# demux1-10.net
KiCad netlist of a schematic drawn in Altium Designer
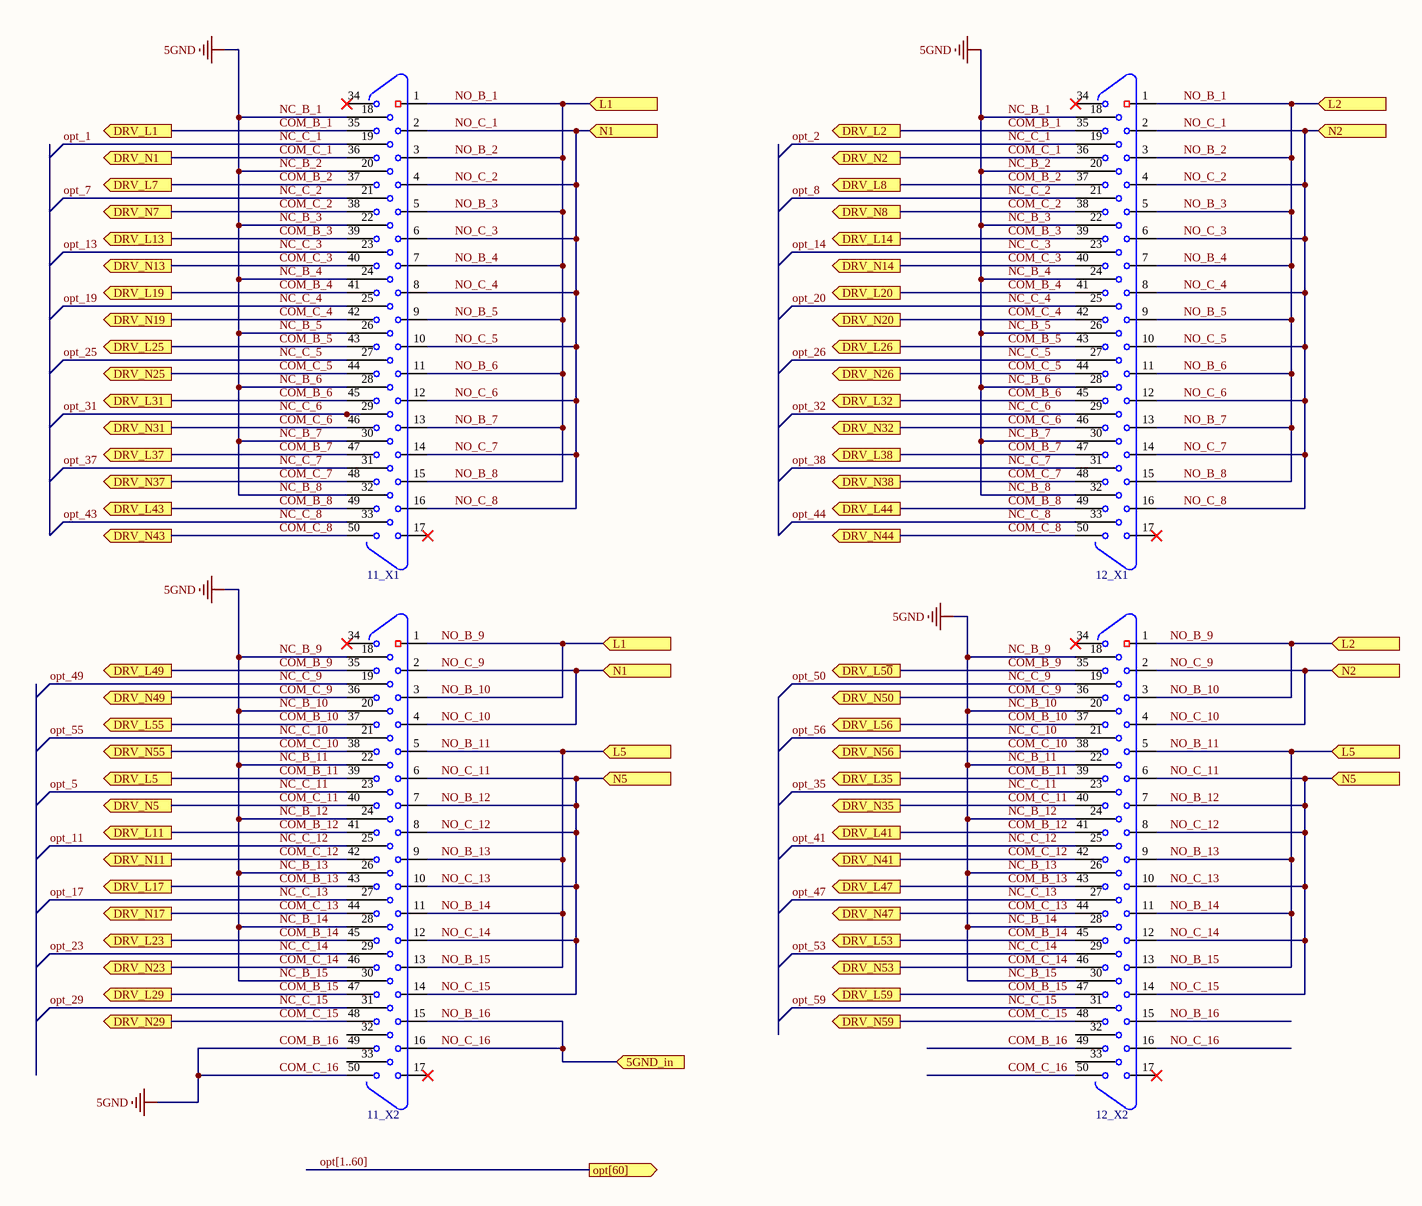
[diagram p0: demux1-10.SchDoc, left]
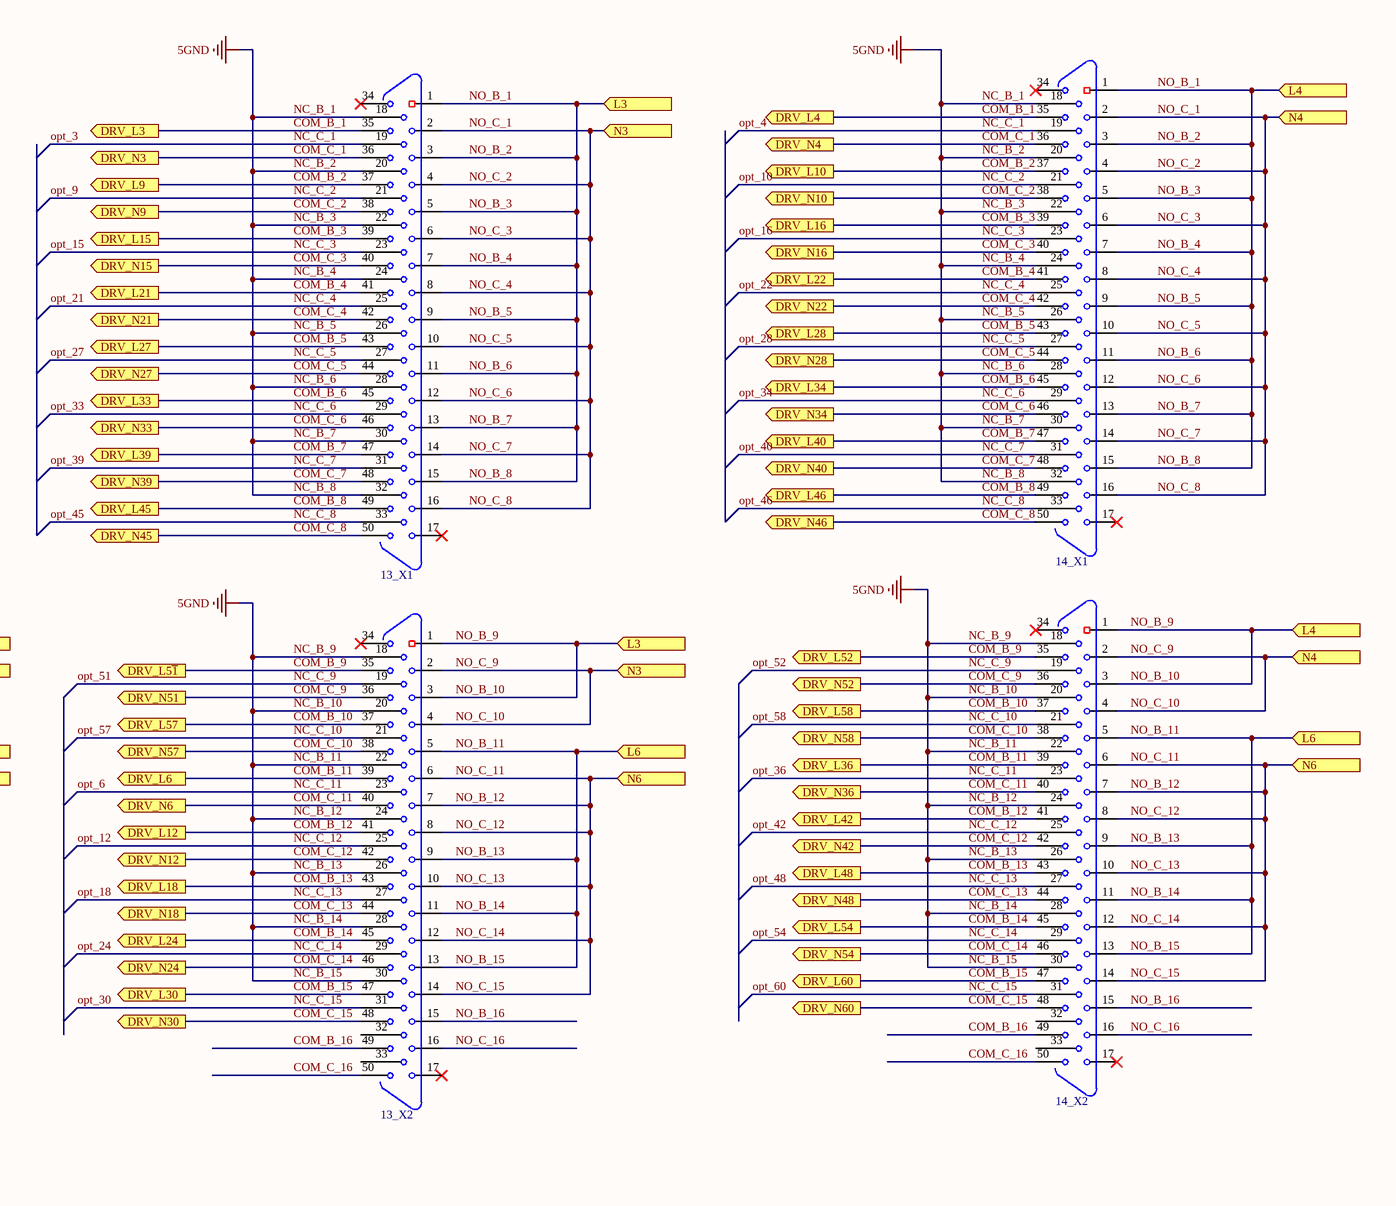
[diagram p1: demux1-10.SchDoc, right]

(export (version "E")
  (design (tool "Eeschema 10.0.6"))
  (components
    (comp (ref "11_X1") (value "DB50") (footprint "DB50_RA") (libsource (lib "WIRE") (part "DB50")))
    (comp (ref "11_X2") (value "DB50") (footprint "DB50_RA") (libsource (lib "WIRE") (part "DB50")))
    (comp (ref "12_X1") (value "DB50") (footprint "DB50_RA") (libsource (lib "WIRE") (part "DB50")))
    (comp (ref "12_X2") (value "DB50") (footprint "DB50_RA") (libsource (lib "WIRE") (part "DB50")))
    (comp (ref "13_X1") (value "DB50") (footprint "DB50_RA") (libsource (lib "WIRE") (part "DB50")))
    (comp (ref "13_X2") (value "DB50") (footprint "DB50_RA") (libsource (lib "WIRE") (part "DB50")))
    (comp (ref "14_X1") (value "DB50") (footprint "DB50_RA") (libsource (lib "WIRE") (part "DB50")))
    (comp (ref "14_X2") (value "DB50") (footprint "DB50_RA") (libsource (lib "WIRE") (part "DB50")))
  )
  (nets
    (net (code "61") (name "/COM_B_1") (class "Default")
      (node (ref "11_X1") (pin "35") (pinfunction "35_35") (pintype "passive"))
      (node (ref "12_X1") (pin "35") (pinfunction "35_35") (pintype "passive"))
      (node (ref "13_X1") (pin "35") (pinfunction "35_35") (pintype "passive"))
      (node (ref "14_X1") (pin "35") (pinfunction "35_35") (pintype "passive"))
    )
    (net (code "62") (name "/COM_B_2") (class "Default")
      (node (ref "11_X1") (pin "37") (pinfunction "37_37") (pintype "passive"))
      (node (ref "12_X1") (pin "37") (pinfunction "37_37") (pintype "passive"))
      (node (ref "13_X1") (pin "37") (pinfunction "37_37") (pintype "passive"))
      (node (ref "14_X1") (pin "37") (pinfunction "37_37") (pintype "passive"))
    )
    (net (code "63") (name "/COM_B_3") (class "Default")
      (node (ref "11_X1") (pin "39") (pinfunction "39_39") (pintype "passive"))
      (node (ref "12_X1") (pin "39") (pinfunction "39_39") (pintype "passive"))
      (node (ref "13_X1") (pin "39") (pinfunction "39_39") (pintype "passive"))
      (node (ref "14_X1") (pin "39") (pinfunction "39_39") (pintype "passive"))
    )
    (net (code "64") (name "/COM_B_4") (class "Default")
      (node (ref "11_X1") (pin "41") (pinfunction "41_41") (pintype "passive"))
      (node (ref "12_X1") (pin "41") (pinfunction "41_41") (pintype "passive"))
      (node (ref "13_X1") (pin "41") (pinfunction "41_41") (pintype "passive"))
      (node (ref "14_X1") (pin "41") (pinfunction "41_41") (pintype "passive"))
    )
    (net (code "65") (name "/COM_B_5") (class "Default")
      (node (ref "11_X1") (pin "43") (pinfunction "43_43") (pintype "passive"))
      (node (ref "12_X1") (pin "43") (pinfunction "43_43") (pintype "passive"))
      (node (ref "13_X1") (pin "43") (pinfunction "43_43") (pintype "passive"))
      (node (ref "14_X1") (pin "43") (pinfunction "43_43") (pintype "passive"))
    )
    (net (code "66") (name "/COM_B_6") (class "Default")
      (node (ref "11_X1") (pin "45") (pinfunction "45_45") (pintype "passive"))
      (node (ref "12_X1") (pin "45") (pinfunction "45_45") (pintype "passive"))
      (node (ref "13_X1") (pin "45") (pinfunction "45_45") (pintype "passive"))
      (node (ref "14_X1") (pin "45") (pinfunction "45_45") (pintype "passive"))
    )
    (net (code "67") (name "/COM_B_7") (class "Default")
      (node (ref "11_X1") (pin "47") (pinfunction "47_47") (pintype "passive"))
      (node (ref "12_X1") (pin "47") (pinfunction "47_47") (pintype "passive"))
      (node (ref "13_X1") (pin "47") (pinfunction "47_47") (pintype "passive"))
      (node (ref "14_X1") (pin "47") (pinfunction "47_47") (pintype "passive"))
    )
    (net (code "68") (name "/COM_B_8") (class "Default")
      (node (ref "11_X1") (pin "49") (pinfunction "49_49") (pintype "passive"))
      (node (ref "12_X1") (pin "49") (pinfunction "49_49") (pintype "passive"))
      (node (ref "13_X1") (pin "49") (pinfunction "49_49") (pintype "passive"))
      (node (ref "14_X1") (pin "49") (pinfunction "49_49") (pintype "passive"))
    )
    (net (code "69") (name "/COM_B_9") (class "Default")
      (node (ref "11_X2") (pin "35") (pinfunction "35_35") (pintype "passive"))
      (node (ref "12_X2") (pin "35") (pinfunction "35_35") (pintype "passive"))
      (node (ref "13_X2") (pin "35") (pinfunction "35_35") (pintype "passive"))
      (node (ref "14_X2") (pin "35") (pinfunction "35_35") (pintype "passive"))
    )
    (net (code "70") (name "/COM_B_10") (class "Default")
      (node (ref "11_X2") (pin "37") (pinfunction "37_37") (pintype "passive"))
      (node (ref "12_X2") (pin "37") (pinfunction "37_37") (pintype "passive"))
      (node (ref "13_X2") (pin "37") (pinfunction "37_37") (pintype "passive"))
      (node (ref "14_X2") (pin "37") (pinfunction "37_37") (pintype "passive"))
    )
    (net (code "71") (name "/COM_B_11") (class "Default")
      (node (ref "11_X2") (pin "39") (pinfunction "39_39") (pintype "passive"))
      (node (ref "12_X2") (pin "39") (pinfunction "39_39") (pintype "passive"))
      (node (ref "13_X2") (pin "39") (pinfunction "39_39") (pintype "passive"))
      (node (ref "14_X2") (pin "39") (pinfunction "39_39") (pintype "passive"))
    )
    (net (code "72") (name "/COM_B_12") (class "Default")
      (node (ref "11_X2") (pin "41") (pinfunction "41_41") (pintype "passive"))
      (node (ref "12_X2") (pin "41") (pinfunction "41_41") (pintype "passive"))
      (node (ref "13_X2") (pin "41") (pinfunction "41_41") (pintype "passive"))
      (node (ref "14_X2") (pin "41") (pinfunction "41_41") (pintype "passive"))
    )
    (net (code "73") (name "/COM_B_13") (class "Default")
      (node (ref "11_X2") (pin "43") (pinfunction "43_43") (pintype "passive"))
      (node (ref "12_X2") (pin "43") (pinfunction "43_43") (pintype "passive"))
      (node (ref "13_X2") (pin "43") (pinfunction "43_43") (pintype "passive"))
      (node (ref "14_X2") (pin "43") (pinfunction "43_43") (pintype "passive"))
    )
    (net (code "74") (name "/COM_B_14") (class "Default")
      (node (ref "11_X2") (pin "45") (pinfunction "45_45") (pintype "passive"))
      (node (ref "12_X2") (pin "45") (pinfunction "45_45") (pintype "passive"))
      (node (ref "13_X2") (pin "45") (pinfunction "45_45") (pintype "passive"))
      (node (ref "14_X2") (pin "45") (pinfunction "45_45") (pintype "passive"))
    )
    (net (code "75") (name "/COM_B_15") (class "Default")
      (node (ref "11_X2") (pin "47") (pinfunction "47_47") (pintype "passive"))
      (node (ref "12_X2") (pin "47") (pinfunction "47_47") (pintype "passive"))
      (node (ref "13_X2") (pin "47") (pinfunction "47_47") (pintype "passive"))
      (node (ref "14_X2") (pin "47") (pinfunction "47_47") (pintype "passive"))
    )
    (net (code "76") (name "/COM_C_1") (class "Default")
      (node (ref "11_X1") (pin "36") (pinfunction "36_36") (pintype "passive"))
      (node (ref "12_X1") (pin "36") (pinfunction "36_36") (pintype "passive"))
      (node (ref "13_X1") (pin "36") (pinfunction "36_36") (pintype "passive"))
      (node (ref "14_X1") (pin "36") (pinfunction "36_36") (pintype "passive"))
    )
    (net (code "77") (name "/COM_C_2") (class "Default")
      (node (ref "11_X1") (pin "38") (pinfunction "38_38") (pintype "passive"))
      (node (ref "12_X1") (pin "38") (pinfunction "38_38") (pintype "passive"))
      (node (ref "13_X1") (pin "38") (pinfunction "38_38") (pintype "passive"))
      (node (ref "14_X1") (pin "38") (pinfunction "38_38") (pintype "passive"))
    )
    (net (code "78") (name "/COM_C_3") (class "Default")
      (node (ref "11_X1") (pin "40") (pinfunction "40_40") (pintype "passive"))
      (node (ref "12_X1") (pin "40") (pinfunction "40_40") (pintype "passive"))
      (node (ref "13_X1") (pin "40") (pinfunction "40_40") (pintype "passive"))
      (node (ref "14_X1") (pin "40") (pinfunction "40_40") (pintype "passive"))
    )
    (net (code "79") (name "/COM_C_4") (class "Default")
      (node (ref "11_X1") (pin "42") (pinfunction "42_42") (pintype "passive"))
      (node (ref "12_X1") (pin "42") (pinfunction "42_42") (pintype "passive"))
      (node (ref "13_X1") (pin "42") (pinfunction "42_42") (pintype "passive"))
      (node (ref "14_X1") (pin "42") (pinfunction "42_42") (pintype "passive"))
    )
    (net (code "80") (name "/COM_C_5") (class "Default")
      (node (ref "11_X1") (pin "44") (pinfunction "44_44") (pintype "passive"))
      (node (ref "12_X1") (pin "44") (pinfunction "44_44") (pintype "passive"))
      (node (ref "13_X1") (pin "44") (pinfunction "44_44") (pintype "passive"))
      (node (ref "14_X1") (pin "44") (pinfunction "44_44") (pintype "passive"))
    )
    (net (code "81") (name "/COM_C_6") (class "Default")
      (node (ref "11_X1") (pin "46") (pinfunction "46_46") (pintype "passive"))
      (node (ref "12_X1") (pin "46") (pinfunction "46_46") (pintype "passive"))
      (node (ref "13_X1") (pin "46") (pinfunction "46_46") (pintype "passive"))
      (node (ref "14_X1") (pin "46") (pinfunction "46_46") (pintype "passive"))
    )
    (net (code "82") (name "/COM_C_7") (class "Default")
      (node (ref "11_X1") (pin "48") (pinfunction "48_48") (pintype "passive"))
      (node (ref "12_X1") (pin "48") (pinfunction "48_48") (pintype "passive"))
      (node (ref "13_X1") (pin "48") (pinfunction "48_48") (pintype "passive"))
      (node (ref "14_X1") (pin "48") (pinfunction "48_48") (pintype "passive"))
    )
    (net (code "83") (name "/COM_C_8") (class "Default")
      (node (ref "11_X1") (pin "50") (pinfunction "50_50") (pintype "passive"))
      (node (ref "12_X1") (pin "50") (pinfunction "50_50") (pintype "passive"))
      (node (ref "13_X1") (pin "50") (pinfunction "50_50") (pintype "passive"))
      (node (ref "14_X1") (pin "50") (pinfunction "50_50") (pintype "passive"))
    )
    (net (code "84") (name "/COM_C_9") (class "Default")
      (node (ref "11_X2") (pin "36") (pinfunction "36_36") (pintype "passive"))
      (node (ref "12_X2") (pin "36") (pinfunction "36_36") (pintype "passive"))
      (node (ref "13_X2") (pin "36") (pinfunction "36_36") (pintype "passive"))
      (node (ref "14_X2") (pin "36") (pinfunction "36_36") (pintype "passive"))
    )
    (net (code "85") (name "/COM_C_10") (class "Default")
      (node (ref "11_X2") (pin "38") (pinfunction "38_38") (pintype "passive"))
      (node (ref "12_X2") (pin "38") (pinfunction "38_38") (pintype "passive"))
      (node (ref "13_X2") (pin "38") (pinfunction "38_38") (pintype "passive"))
      (node (ref "14_X2") (pin "38") (pinfunction "38_38") (pintype "passive"))
    )
    (net (code "86") (name "/COM_C_11") (class "Default")
      (node (ref "11_X2") (pin "40") (pinfunction "40_40") (pintype "passive"))
      (node (ref "12_X2") (pin "40") (pinfunction "40_40") (pintype "passive"))
      (node (ref "13_X2") (pin "40") (pinfunction "40_40") (pintype "passive"))
      (node (ref "14_X2") (pin "40") (pinfunction "40_40") (pintype "passive"))
    )
    (net (code "87") (name "/COM_C_12") (class "Default")
      (node (ref "11_X2") (pin "42") (pinfunction "42_42") (pintype "passive"))
      (node (ref "12_X2") (pin "42") (pinfunction "42_42") (pintype "passive"))
      (node (ref "13_X2") (pin "42") (pinfunction "42_42") (pintype "passive"))
      (node (ref "14_X2") (pin "42") (pinfunction "42_42") (pintype "passive"))
    )
    (net (code "88") (name "/COM_C_13") (class "Default")
      (node (ref "11_X2") (pin "44") (pinfunction "44_44") (pintype "passive"))
      (node (ref "12_X2") (pin "44") (pinfunction "44_44") (pintype "passive"))
      (node (ref "13_X2") (pin "44") (pinfunction "44_44") (pintype "passive"))
      (node (ref "14_X2") (pin "44") (pinfunction "44_44") (pintype "passive"))
    )
    (net (code "89") (name "/COM_C_14") (class "Default")
      (node (ref "11_X2") (pin "46") (pinfunction "46_46") (pintype "passive"))
      (node (ref "12_X2") (pin "46") (pinfunction "46_46") (pintype "passive"))
      (node (ref "13_X2") (pin "46") (pinfunction "46_46") (pintype "passive"))
      (node (ref "14_X2") (pin "46") (pinfunction "46_46") (pintype "passive"))
    )
    (net (code "90") (name "/COM_C_15") (class "Default")
      (node (ref "11_X2") (pin "48") (pinfunction "48_48") (pintype "passive"))
      (node (ref "12_X2") (pin "48") (pinfunction "48_48") (pintype "passive"))
      (node (ref "13_X2") (pin "48") (pinfunction "48_48") (pintype "passive"))
      (node (ref "14_X2") (pin "48") (pinfunction "48_48") (pintype "passive"))
    )
    (net (code "91") (name "/NC_C_1") (class "Default")
      (node (ref "11_X1") (pin "19") (pinfunction "19_19") (pintype "passive"))
      (node (ref "12_X1") (pin "19") (pinfunction "19_19") (pintype "passive"))
      (node (ref "13_X1") (pin "19") (pinfunction "19_19") (pintype "passive"))
      (node (ref "14_X1") (pin "19") (pinfunction "19_19") (pintype "passive"))
    )
    (net (code "92") (name "/NC_C_2") (class "Default")
      (node (ref "11_X1") (pin "21") (pinfunction "21_21") (pintype "passive"))
      (node (ref "12_X1") (pin "21") (pinfunction "21_21") (pintype "passive"))
      (node (ref "13_X1") (pin "21") (pinfunction "21_21") (pintype "passive"))
      (node (ref "14_X1") (pin "21") (pinfunction "21_21") (pintype "passive"))
    )
    (net (code "93") (name "/NC_C_3") (class "Default")
      (node (ref "11_X1") (pin "23") (pinfunction "23_23") (pintype "passive"))
      (node (ref "12_X1") (pin "23") (pinfunction "23_23") (pintype "passive"))
      (node (ref "13_X1") (pin "23") (pinfunction "23_23") (pintype "passive"))
      (node (ref "14_X1") (pin "23") (pinfunction "23_23") (pintype "passive"))
    )
    (net (code "94") (name "/NC_C_4") (class "Default")
      (node (ref "11_X1") (pin "25") (pinfunction "3_25") (pintype "passive"))
      (node (ref "12_X1") (pin "25") (pinfunction "3_25") (pintype "passive"))
      (node (ref "13_X1") (pin "25") (pinfunction "3_25") (pintype "passive"))
      (node (ref "14_X1") (pin "25") (pinfunction "3_25") (pintype "passive"))
    )
    (net (code "95") (name "/NC_C_5") (class "Default")
      (node (ref "11_X1") (pin "27") (pinfunction "27_27") (pintype "passive"))
      (node (ref "12_X1") (pin "27") (pinfunction "27_27") (pintype "passive"))
      (node (ref "13_X1") (pin "27") (pinfunction "27_27") (pintype "passive"))
      (node (ref "14_X1") (pin "27") (pinfunction "27_27") (pintype "passive"))
    )
    (net (code "96") (name "/NC_C_6") (class "Default")
      (node (ref "11_X1") (pin "29") (pinfunction "29_29") (pintype "passive"))
      (node (ref "12_X1") (pin "29") (pinfunction "29_29") (pintype "passive"))
      (node (ref "13_X1") (pin "29") (pinfunction "29_29") (pintype "passive"))
      (node (ref "14_X1") (pin "29") (pinfunction "29_29") (pintype "passive"))
    )
    (net (code "97") (name "/NC_C_7") (class "Default")
      (node (ref "11_X1") (pin "31") (pinfunction "31_31") (pintype "passive"))
      (node (ref "12_X1") (pin "31") (pinfunction "31_31") (pintype "passive"))
      (node (ref "13_X1") (pin "31") (pinfunction "31_31") (pintype "passive"))
      (node (ref "14_X1") (pin "31") (pinfunction "31_31") (pintype "passive"))
    )
    (net (code "98") (name "/NC_C_8") (class "Default")
      (node (ref "11_X1") (pin "33") (pinfunction "33_33") (pintype "passive"))
      (node (ref "12_X1") (pin "33") (pinfunction "33_33") (pintype "passive"))
      (node (ref "13_X1") (pin "33") (pinfunction "33_33") (pintype "passive"))
      (node (ref "14_X1") (pin "33") (pinfunction "33_33") (pintype "passive"))
    )
    (net (code "99") (name "/NC_C_9") (class "Default")
      (node (ref "11_X2") (pin "19") (pinfunction "19_19") (pintype "passive"))
      (node (ref "12_X2") (pin "19") (pinfunction "19_19") (pintype "passive"))
      (node (ref "13_X2") (pin "19") (pinfunction "19_19") (pintype "passive"))
      (node (ref "14_X2") (pin "19") (pinfunction "19_19") (pintype "passive"))
    )
    (net (code "100") (name "/NC_C_10") (class "Default")
      (node (ref "11_X2") (pin "21") (pinfunction "21_21") (pintype "passive"))
      (node (ref "12_X2") (pin "21") (pinfunction "21_21") (pintype "passive"))
      (node (ref "13_X2") (pin "21") (pinfunction "21_21") (pintype "passive"))
      (node (ref "14_X2") (pin "21") (pinfunction "21_21") (pintype "passive"))
    )
    (net (code "101") (name "/NC_C_11") (class "Default")
      (node (ref "11_X2") (pin "23") (pinfunction "23_23") (pintype "passive"))
      (node (ref "12_X2") (pin "23") (pinfunction "23_23") (pintype "passive"))
      (node (ref "13_X2") (pin "23") (pinfunction "23_23") (pintype "passive"))
      (node (ref "14_X2") (pin "23") (pinfunction "23_23") (pintype "passive"))
    )
    (net (code "102") (name "/NC_C_12") (class "Default")
      (node (ref "11_X2") (pin "25") (pinfunction "3_25") (pintype "passive"))
      (node (ref "12_X2") (pin "25") (pinfunction "3_25") (pintype "passive"))
      (node (ref "13_X2") (pin "25") (pinfunction "3_25") (pintype "passive"))
      (node (ref "14_X2") (pin "25") (pinfunction "3_25") (pintype "passive"))
    )
    (net (code "103") (name "/NC_C_13") (class "Default")
      (node (ref "11_X2") (pin "27") (pinfunction "27_27") (pintype "passive"))
      (node (ref "12_X2") (pin "27") (pinfunction "27_27") (pintype "passive"))
      (node (ref "13_X2") (pin "27") (pinfunction "27_27") (pintype "passive"))
      (node (ref "14_X2") (pin "27") (pinfunction "27_27") (pintype "passive"))
    )
    (net (code "104") (name "/NC_C_14") (class "Default")
      (node (ref "11_X2") (pin "29") (pinfunction "29_29") (pintype "passive"))
      (node (ref "12_X2") (pin "29") (pinfunction "29_29") (pintype "passive"))
      (node (ref "13_X2") (pin "29") (pinfunction "29_29") (pintype "passive"))
      (node (ref "14_X2") (pin "29") (pinfunction "29_29") (pintype "passive"))
    )
    (net (code "105") (name "/NC_C_15") (class "Default")
      (node (ref "11_X2") (pin "31") (pinfunction "31_31") (pintype "passive"))
      (node (ref "12_X2") (pin "31") (pinfunction "31_31") (pintype "passive"))
      (node (ref "13_X2") (pin "31") (pinfunction "31_31") (pintype "passive"))
      (node (ref "14_X2") (pin "31") (pinfunction "31_31") (pintype "passive"))
    )
    (net (code "106") (name "/NO_B_1") (class "Default")
      (node (ref "11_X1") (pin "1") (pinfunction "1_1") (pintype "passive"))
      (node (ref "11_X1") (pin "11") (pinfunction "11_11") (pintype "passive"))
      (node (ref "11_X1") (pin "13") (pinfunction "13_13") (pintype "passive"))
      (node (ref "11_X1") (pin "15") (pinfunction "15_15") (pintype "passive"))
      (node (ref "11_X1") (pin "3") (pinfunction "3_3") (pintype "passive"))
      (node (ref "11_X1") (pin "5") (pinfunction "2_5") (pintype "passive"))
      (node (ref "11_X1") (pin "7") (pinfunction "7_7") (pintype "passive"))
      (node (ref "11_X1") (pin "9") (pinfunction "4_9") (pintype "passive"))
      (node (ref "11_X2") (pin "1") (pinfunction "1_1") (pintype "passive"))
      (node (ref "11_X2") (pin "3") (pinfunction "3_3") (pintype "passive"))
      (node (ref "12_X1") (pin "1") (pinfunction "1_1") (pintype "passive"))
      (node (ref "12_X1") (pin "11") (pinfunction "11_11") (pintype "passive"))
      (node (ref "12_X1") (pin "13") (pinfunction "13_13") (pintype "passive"))
      (node (ref "12_X1") (pin "15") (pinfunction "15_15") (pintype "passive"))
      (node (ref "12_X1") (pin "3") (pinfunction "3_3") (pintype "passive"))
      (node (ref "12_X1") (pin "5") (pinfunction "2_5") (pintype "passive"))
      (node (ref "12_X1") (pin "7") (pinfunction "7_7") (pintype "passive"))
      (node (ref "12_X1") (pin "9") (pinfunction "4_9") (pintype "passive"))
      (node (ref "12_X2") (pin "1") (pinfunction "1_1") (pintype "passive"))
      (node (ref "12_X2") (pin "3") (pinfunction "3_3") (pintype "passive"))
      (node (ref "13_X1") (pin "1") (pinfunction "1_1") (pintype "passive"))
      (node (ref "13_X1") (pin "11") (pinfunction "11_11") (pintype "passive"))
      (node (ref "13_X1") (pin "13") (pinfunction "13_13") (pintype "passive"))
      (node (ref "13_X1") (pin "15") (pinfunction "15_15") (pintype "passive"))
      (node (ref "13_X1") (pin "3") (pinfunction "3_3") (pintype "passive"))
      (node (ref "13_X1") (pin "5") (pinfunction "2_5") (pintype "passive"))
      (node (ref "13_X1") (pin "7") (pinfunction "7_7") (pintype "passive"))
      (node (ref "13_X1") (pin "9") (pinfunction "4_9") (pintype "passive"))
      (node (ref "13_X2") (pin "1") (pinfunction "1_1") (pintype "passive"))
      (node (ref "13_X2") (pin "3") (pinfunction "3_3") (pintype "passive"))
      (node (ref "14_X1") (pin "1") (pinfunction "1_1") (pintype "passive"))
      (node (ref "14_X1") (pin "11") (pinfunction "11_11") (pintype "passive"))
      (node (ref "14_X1") (pin "13") (pinfunction "13_13") (pintype "passive"))
      (node (ref "14_X1") (pin "15") (pinfunction "15_15") (pintype "passive"))
      (node (ref "14_X1") (pin "3") (pinfunction "3_3") (pintype "passive"))
      (node (ref "14_X1") (pin "5") (pinfunction "2_5") (pintype "passive"))
      (node (ref "14_X1") (pin "7") (pinfunction "7_7") (pintype "passive"))
      (node (ref "14_X1") (pin "9") (pinfunction "4_9") (pintype "passive"))
      (node (ref "14_X2") (pin "1") (pinfunction "1_1") (pintype "passive"))
      (node (ref "14_X2") (pin "3") (pinfunction "3_3") (pintype "passive"))
    )
    (net (code "107") (name "/NO_B_11") (class "Default")
      (node (ref "11_X2") (pin "11") (pinfunction "11_11") (pintype "passive"))
      (node (ref "11_X2") (pin "13") (pinfunction "13_13") (pintype "passive"))
      (node (ref "11_X2") (pin "5") (pinfunction "2_5") (pintype "passive"))
      (node (ref "11_X2") (pin "9") (pinfunction "4_9") (pintype "passive"))
      (node (ref "12_X2") (pin "11") (pinfunction "11_11") (pintype "passive"))
      (node (ref "12_X2") (pin "13") (pinfunction "13_13") (pintype "passive"))
      (node (ref "12_X2") (pin "5") (pinfunction "2_5") (pintype "passive"))
      (node (ref "12_X2") (pin "9") (pinfunction "4_9") (pintype "passive"))
      (node (ref "13_X2") (pin "11") (pinfunction "11_11") (pintype "passive"))
      (node (ref "13_X2") (pin "13") (pinfunction "13_13") (pintype "passive"))
      (node (ref "13_X2") (pin "5") (pinfunction "2_5") (pintype "passive"))
      (node (ref "13_X2") (pin "9") (pinfunction "4_9") (pintype "passive"))
      (node (ref "14_X2") (pin "11") (pinfunction "11_11") (pintype "passive"))
      (node (ref "14_X2") (pin "13") (pinfunction "13_13") (pintype "passive"))
      (node (ref "14_X2") (pin "5") (pinfunction "2_5") (pintype "passive"))
      (node (ref "14_X2") (pin "9") (pinfunction "4_9") (pintype "passive"))
    )
    (net (code "108") (name "/NO_B_12") (class "Default")
      (node (ref "11_X2") (pin "10") (pinfunction "10_10") (pintype "passive"))
      (node (ref "11_X2") (pin "12") (pinfunction "12_12") (pintype "passive"))
      (node (ref "11_X2") (pin "14") (pinfunction "14_14") (pintype "passive"))
      (node (ref "11_X2") (pin "6") (pinfunction "6_6") (pintype "passive"))
      (node (ref "11_X2") (pin "7") (pinfunction "7_7") (pintype "passive"))
      (node (ref "11_X2") (pin "8") (pinfunction "8_8") (pintype "passive"))
      (node (ref "12_X2") (pin "10") (pinfunction "10_10") (pintype "passive"))
      (node (ref "12_X2") (pin "12") (pinfunction "12_12") (pintype "passive"))
      (node (ref "12_X2") (pin "14") (pinfunction "14_14") (pintype "passive"))
      (node (ref "12_X2") (pin "6") (pinfunction "6_6") (pintype "passive"))
      (node (ref "12_X2") (pin "7") (pinfunction "7_7") (pintype "passive"))
      (node (ref "12_X2") (pin "8") (pinfunction "8_8") (pintype "passive"))
      (node (ref "13_X2") (pin "10") (pinfunction "10_10") (pintype "passive"))
      (node (ref "13_X2") (pin "12") (pinfunction "12_12") (pintype "passive"))
      (node (ref "13_X2") (pin "14") (pinfunction "14_14") (pintype "passive"))
      (node (ref "13_X2") (pin "6") (pinfunction "6_6") (pintype "passive"))
      (node (ref "13_X2") (pin "7") (pinfunction "7_7") (pintype "passive"))
      (node (ref "13_X2") (pin "8") (pinfunction "8_8") (pintype "passive"))
      (node (ref "14_X2") (pin "10") (pinfunction "10_10") (pintype "passive"))
      (node (ref "14_X2") (pin "12") (pinfunction "12_12") (pintype "passive"))
      (node (ref "14_X2") (pin "14") (pinfunction "14_14") (pintype "passive"))
      (node (ref "14_X2") (pin "6") (pinfunction "6_6") (pintype "passive"))
      (node (ref "14_X2") (pin "7") (pinfunction "7_7") (pintype "passive"))
      (node (ref "14_X2") (pin "8") (pinfunction "8_8") (pintype "passive"))
    )
    (net (code "109") (name "/NO_B_16") (class "Default")
      (node (ref "11_X2") (pin "15") (pinfunction "15_15") (pintype "passive"))
      (node (ref "11_X2") (pin "16") (pinfunction "16_16") (pintype "passive"))
      (node (ref "12_X2") (pin "15") (pinfunction "15_15") (pintype "passive"))
      (node (ref "12_X2") (pin "16") (pinfunction "16_16") (pintype "passive"))
      (node (ref "13_X2") (pin "15") (pinfunction "15_15") (pintype "passive"))
      (node (ref "13_X2") (pin "16") (pinfunction "16_16") (pintype "passive"))
      (node (ref "14_X2") (pin "15") (pinfunction "15_15") (pintype "passive"))
      (node (ref "14_X2") (pin "16") (pinfunction "16_16") (pintype "passive"))
    )
    (net (code "110") (name "/NO_C_1") (class "Default")
      (node (ref "11_X1") (pin "10") (pinfunction "10_10") (pintype "passive"))
      (node (ref "11_X1") (pin "12") (pinfunction "12_12") (pintype "passive"))
      (node (ref "11_X1") (pin "14") (pinfunction "14_14") (pintype "passive"))
      (node (ref "11_X1") (pin "16") (pinfunction "16_16") (pintype "passive"))
      (node (ref "11_X1") (pin "2") (pinfunction "2_2") (pintype "passive"))
      (node (ref "11_X1") (pin "4") (pinfunction "4_4") (pintype "passive"))
      (node (ref "11_X1") (pin "6") (pinfunction "6_6") (pintype "passive"))
      (node (ref "11_X1") (pin "8") (pinfunction "8_8") (pintype "passive"))
      (node (ref "11_X2") (pin "2") (pinfunction "2_2") (pintype "passive"))
      (node (ref "11_X2") (pin "4") (pinfunction "4_4") (pintype "passive"))
      (node (ref "12_X1") (pin "10") (pinfunction "10_10") (pintype "passive"))
      (node (ref "12_X1") (pin "12") (pinfunction "12_12") (pintype "passive"))
      (node (ref "12_X1") (pin "14") (pinfunction "14_14") (pintype "passive"))
      (node (ref "12_X1") (pin "16") (pinfunction "16_16") (pintype "passive"))
      (node (ref "12_X1") (pin "2") (pinfunction "2_2") (pintype "passive"))
      (node (ref "12_X1") (pin "4") (pinfunction "4_4") (pintype "passive"))
      (node (ref "12_X1") (pin "6") (pinfunction "6_6") (pintype "passive"))
      (node (ref "12_X1") (pin "8") (pinfunction "8_8") (pintype "passive"))
      (node (ref "12_X2") (pin "2") (pinfunction "2_2") (pintype "passive"))
      (node (ref "12_X2") (pin "4") (pinfunction "4_4") (pintype "passive"))
      (node (ref "13_X1") (pin "10") (pinfunction "10_10") (pintype "passive"))
      (node (ref "13_X1") (pin "12") (pinfunction "12_12") (pintype "passive"))
      (node (ref "13_X1") (pin "14") (pinfunction "14_14") (pintype "passive"))
      (node (ref "13_X1") (pin "16") (pinfunction "16_16") (pintype "passive"))
      (node (ref "13_X1") (pin "2") (pinfunction "2_2") (pintype "passive"))
      (node (ref "13_X1") (pin "4") (pinfunction "4_4") (pintype "passive"))
      (node (ref "13_X1") (pin "6") (pinfunction "6_6") (pintype "passive"))
      (node (ref "13_X1") (pin "8") (pinfunction "8_8") (pintype "passive"))
      (node (ref "13_X2") (pin "2") (pinfunction "2_2") (pintype "passive"))
      (node (ref "13_X2") (pin "4") (pinfunction "4_4") (pintype "passive"))
      (node (ref "14_X1") (pin "10") (pinfunction "10_10") (pintype "passive"))
      (node (ref "14_X1") (pin "12") (pinfunction "12_12") (pintype "passive"))
      (node (ref "14_X1") (pin "14") (pinfunction "14_14") (pintype "passive"))
      (node (ref "14_X1") (pin "16") (pinfunction "16_16") (pintype "passive"))
      (node (ref "14_X1") (pin "2") (pinfunction "2_2") (pintype "passive"))
      (node (ref "14_X1") (pin "4") (pinfunction "4_4") (pintype "passive"))
      (node (ref "14_X1") (pin "6") (pinfunction "6_6") (pintype "passive"))
      (node (ref "14_X1") (pin "8") (pinfunction "8_8") (pintype "passive"))
      (node (ref "14_X2") (pin "2") (pinfunction "2_2") (pintype "passive"))
      (node (ref "14_X2") (pin "4") (pinfunction "4_4") (pintype "passive"))
    )
    (net (code "112") (name "5GND") (class "Default")
      (node (ref "11_X1") (pin "18") (pinfunction "18_18") (pintype "passive"))
      (node (ref "11_X1") (pin "20") (pinfunction "20_20") (pintype "passive"))
      (node (ref "11_X1") (pin "22") (pinfunction "22_22") (pintype "passive"))
      (node (ref "11_X1") (pin "24") (pinfunction "7_24") (pintype "passive"))
      (node (ref "11_X1") (pin "26") (pinfunction "26_26") (pintype "passive"))
      (node (ref "11_X1") (pin "28") (pinfunction "28_28") (pintype "passive"))
      (node (ref "11_X1") (pin "30") (pinfunction "30_30") (pintype "passive"))
      (node (ref "11_X1") (pin "32") (pinfunction "32_32") (pintype "passive"))
      (node (ref "11_X2") (pin "18") (pinfunction "18_18") (pintype "passive"))
      (node (ref "11_X2") (pin "20") (pinfunction "20_20") (pintype "passive"))
      (node (ref "11_X2") (pin "22") (pinfunction "22_22") (pintype "passive"))
      (node (ref "11_X2") (pin "24") (pinfunction "7_24") (pintype "passive"))
      (node (ref "11_X2") (pin "26") (pinfunction "26_26") (pintype "passive"))
      (node (ref "11_X2") (pin "28") (pinfunction "28_28") (pintype "passive"))
      (node (ref "11_X2") (pin "30") (pinfunction "30_30") (pintype "passive"))
      (node (ref "11_X2") (pin "49") (pinfunction "49_49") (pintype "passive"))
      (node (ref "11_X2") (pin "50") (pinfunction "50_50") (pintype "passive"))
      (node (ref "12_X1") (pin "18") (pinfunction "18_18") (pintype "passive"))
      (node (ref "12_X1") (pin "20") (pinfunction "20_20") (pintype "passive"))
      (node (ref "12_X1") (pin "22") (pinfunction "22_22") (pintype "passive"))
      (node (ref "12_X1") (pin "24") (pinfunction "7_24") (pintype "passive"))
      (node (ref "12_X1") (pin "26") (pinfunction "26_26") (pintype "passive"))
      (node (ref "12_X1") (pin "28") (pinfunction "28_28") (pintype "passive"))
      (node (ref "12_X1") (pin "30") (pinfunction "30_30") (pintype "passive"))
      (node (ref "12_X1") (pin "32") (pinfunction "32_32") (pintype "passive"))
      (node (ref "12_X2") (pin "18") (pinfunction "18_18") (pintype "passive"))
      (node (ref "12_X2") (pin "20") (pinfunction "20_20") (pintype "passive"))
      (node (ref "12_X2") (pin "22") (pinfunction "22_22") (pintype "passive"))
      (node (ref "12_X2") (pin "24") (pinfunction "7_24") (pintype "passive"))
      (node (ref "12_X2") (pin "26") (pinfunction "26_26") (pintype "passive"))
      (node (ref "12_X2") (pin "28") (pinfunction "28_28") (pintype "passive"))
      (node (ref "12_X2") (pin "30") (pinfunction "30_30") (pintype "passive"))
      (node (ref "12_X2") (pin "49") (pinfunction "49_49") (pintype "passive"))
      (node (ref "12_X2") (pin "50") (pinfunction "50_50") (pintype "passive"))
      (node (ref "13_X1") (pin "18") (pinfunction "18_18") (pintype "passive"))
      (node (ref "13_X1") (pin "20") (pinfunction "20_20") (pintype "passive"))
      (node (ref "13_X1") (pin "22") (pinfunction "22_22") (pintype "passive"))
      (node (ref "13_X1") (pin "24") (pinfunction "7_24") (pintype "passive"))
      (node (ref "13_X1") (pin "26") (pinfunction "26_26") (pintype "passive"))
      (node (ref "13_X1") (pin "28") (pinfunction "28_28") (pintype "passive"))
      (node (ref "13_X1") (pin "30") (pinfunction "30_30") (pintype "passive"))
      (node (ref "13_X1") (pin "32") (pinfunction "32_32") (pintype "passive"))
      (node (ref "13_X2") (pin "18") (pinfunction "18_18") (pintype "passive"))
      (node (ref "13_X2") (pin "20") (pinfunction "20_20") (pintype "passive"))
      (node (ref "13_X2") (pin "22") (pinfunction "22_22") (pintype "passive"))
      (node (ref "13_X2") (pin "24") (pinfunction "7_24") (pintype "passive"))
      (node (ref "13_X2") (pin "26") (pinfunction "26_26") (pintype "passive"))
      (node (ref "13_X2") (pin "28") (pinfunction "28_28") (pintype "passive"))
      (node (ref "13_X2") (pin "30") (pinfunction "30_30") (pintype "passive"))
      (node (ref "13_X2") (pin "49") (pinfunction "49_49") (pintype "passive"))
      (node (ref "13_X2") (pin "50") (pinfunction "50_50") (pintype "passive"))
      (node (ref "14_X1") (pin "18") (pinfunction "18_18") (pintype "passive"))
      (node (ref "14_X1") (pin "20") (pinfunction "20_20") (pintype "passive"))
      (node (ref "14_X1") (pin "22") (pinfunction "22_22") (pintype "passive"))
      (node (ref "14_X1") (pin "24") (pinfunction "7_24") (pintype "passive"))
      (node (ref "14_X1") (pin "26") (pinfunction "26_26") (pintype "passive"))
      (node (ref "14_X1") (pin "28") (pinfunction "28_28") (pintype "passive"))
      (node (ref "14_X1") (pin "30") (pinfunction "30_30") (pintype "passive"))
      (node (ref "14_X1") (pin "32") (pinfunction "32_32") (pintype "passive"))
      (node (ref "14_X2") (pin "18") (pinfunction "18_18") (pintype "passive"))
      (node (ref "14_X2") (pin "20") (pinfunction "20_20") (pintype "passive"))
      (node (ref "14_X2") (pin "22") (pinfunction "22_22") (pintype "passive"))
      (node (ref "14_X2") (pin "24") (pinfunction "7_24") (pintype "passive"))
      (node (ref "14_X2") (pin "26") (pinfunction "26_26") (pintype "passive"))
      (node (ref "14_X2") (pin "28") (pinfunction "28_28") (pintype "passive"))
      (node (ref "14_X2") (pin "30") (pinfunction "30_30") (pintype "passive"))
      (node (ref "14_X2") (pin "49") (pinfunction "49_49") (pintype "passive"))
      (node (ref "14_X2") (pin "50") (pinfunction "50_50") (pintype "passive"))
    )
    (net (code "113") (name "unconnected-(11_X1-Pad17)") (class "Default")
      (node (ref "11_X1") (pin "17") (pinfunction "17_17") (pintype "passive+no_connect"))
    )
    (net (code "114") (name "unconnected-(11_X1-Pad34)") (class "Default")
      (node (ref "11_X1") (pin "34") (pinfunction "34_34") (pintype "passive+no_connect"))
    )
    (net (code "115") (name "unconnected-(11_X2-Pad17)") (class "Default")
      (node (ref "11_X2") (pin "17") (pinfunction "17_17") (pintype "passive+no_connect"))
    )
    (net (code "116") (name "unconnected-(11_X2-Pad32)") (class "Default")
      (node (ref "11_X2") (pin "32") (pinfunction "32_32") (pintype "passive"))
    )
    (net (code "117") (name "unconnected-(11_X2-Pad33)") (class "Default")
      (node (ref "11_X2") (pin "33") (pinfunction "33_33") (pintype "passive"))
    )
    (net (code "118") (name "unconnected-(11_X2-Pad34)") (class "Default")
      (node (ref "11_X2") (pin "34") (pinfunction "34_34") (pintype "passive+no_connect"))
    )
    (net (code "119") (name "unconnected-(12_X1-Pad17)") (class "Default")
      (node (ref "12_X1") (pin "17") (pinfunction "17_17") (pintype "passive+no_connect"))
    )
    (net (code "120") (name "unconnected-(12_X1-Pad34)") (class "Default")
      (node (ref "12_X1") (pin "34") (pinfunction "34_34") (pintype "passive+no_connect"))
    )
    (net (code "121") (name "unconnected-(12_X2-Pad17)") (class "Default")
      (node (ref "12_X2") (pin "17") (pinfunction "17_17") (pintype "passive+no_connect"))
    )
    (net (code "122") (name "unconnected-(12_X2-Pad32)") (class "Default")
      (node (ref "12_X2") (pin "32") (pinfunction "32_32") (pintype "passive"))
    )
    (net (code "123") (name "unconnected-(12_X2-Pad33)") (class "Default")
      (node (ref "12_X2") (pin "33") (pinfunction "33_33") (pintype "passive"))
    )
    (net (code "124") (name "unconnected-(12_X2-Pad34)") (class "Default")
      (node (ref "12_X2") (pin "34") (pinfunction "34_34") (pintype "passive+no_connect"))
    )
    (net (code "125") (name "unconnected-(13_X1-Pad17)") (class "Default")
      (node (ref "13_X1") (pin "17") (pinfunction "17_17") (pintype "passive+no_connect"))
    )
    (net (code "126") (name "unconnected-(13_X1-Pad34)") (class "Default")
      (node (ref "13_X1") (pin "34") (pinfunction "34_34") (pintype "passive+no_connect"))
    )
    (net (code "127") (name "unconnected-(13_X2-Pad17)") (class "Default")
      (node (ref "13_X2") (pin "17") (pinfunction "17_17") (pintype "passive+no_connect"))
    )
    (net (code "128") (name "unconnected-(13_X2-Pad32)") (class "Default")
      (node (ref "13_X2") (pin "32") (pinfunction "32_32") (pintype "passive"))
    )
    (net (code "129") (name "unconnected-(13_X2-Pad33)") (class "Default")
      (node (ref "13_X2") (pin "33") (pinfunction "33_33") (pintype "passive"))
    )
    (net (code "130") (name "unconnected-(13_X2-Pad34)") (class "Default")
      (node (ref "13_X2") (pin "34") (pinfunction "34_34") (pintype "passive+no_connect"))
    )
    (net (code "131") (name "unconnected-(14_X1-Pad17)") (class "Default")
      (node (ref "14_X1") (pin "17") (pinfunction "17_17") (pintype "passive+no_connect"))
    )
    (net (code "132") (name "unconnected-(14_X1-Pad34)") (class "Default")
      (node (ref "14_X1") (pin "34") (pinfunction "34_34") (pintype "passive+no_connect"))
    )
    (net (code "133") (name "unconnected-(14_X2-Pad17)") (class "Default")
      (node (ref "14_X2") (pin "17") (pinfunction "17_17") (pintype "passive+no_connect"))
    )
    (net (code "134") (name "unconnected-(14_X2-Pad32)") (class "Default")
      (node (ref "14_X2") (pin "32") (pinfunction "32_32") (pintype "passive"))
    )
    (net (code "135") (name "unconnected-(14_X2-Pad33)") (class "Default")
      (node (ref "14_X2") (pin "33") (pinfunction "33_33") (pintype "passive"))
    )
    (net (code "136") (name "unconnected-(14_X2-Pad34)") (class "Default")
      (node (ref "14_X2") (pin "34") (pinfunction "34_34") (pintype "passive+no_connect"))
    )
  )
)
